# MCU.net
KiCad netlist of a schematic drawn in Altium Designer
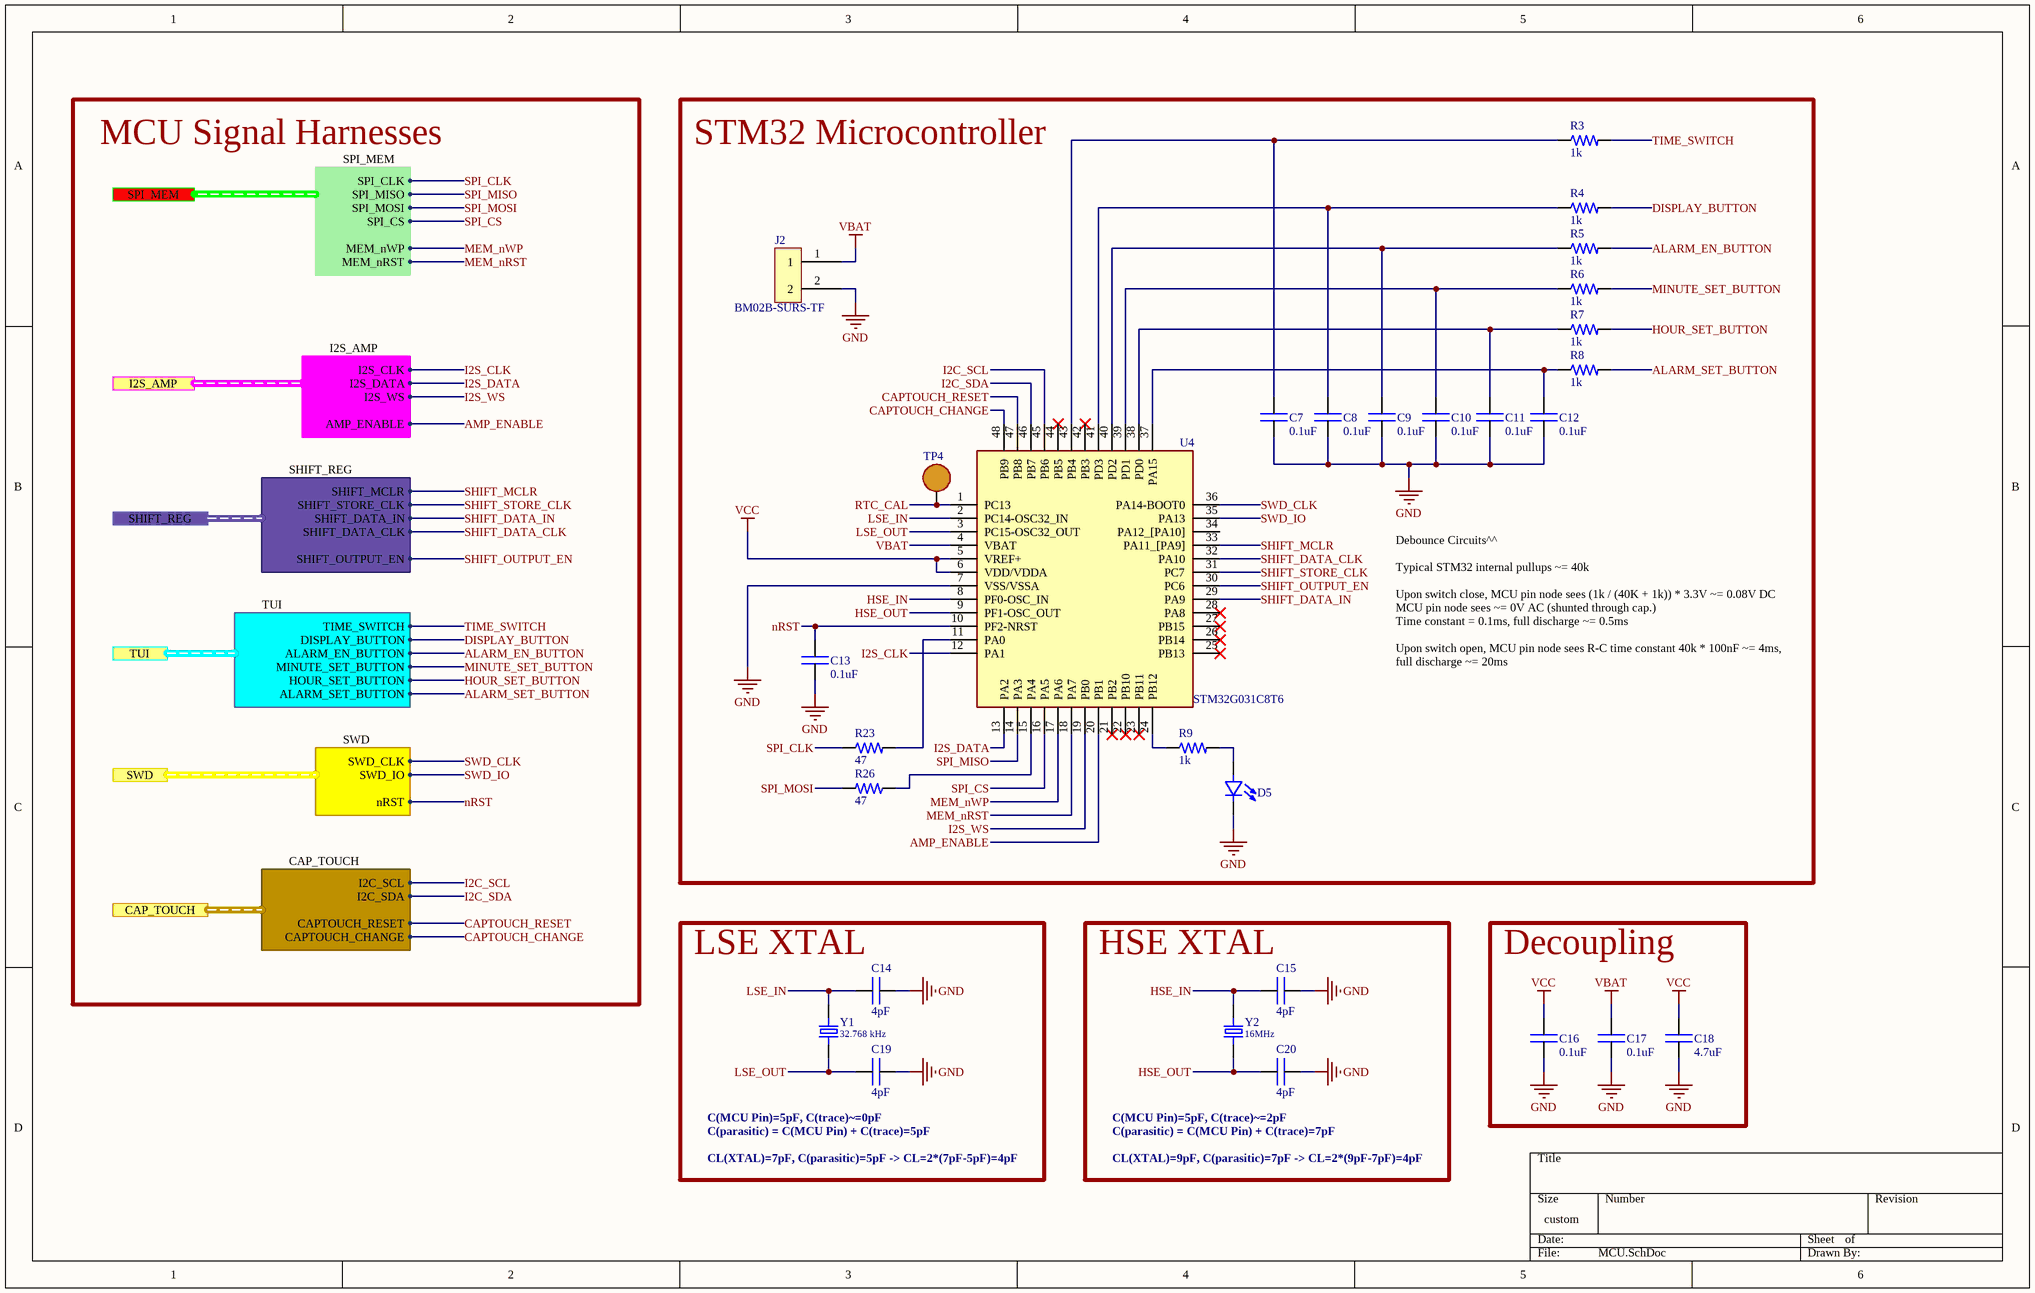
[diagram p0: MCU.SchDoc]

(export (version "E")
  (design (tool "Eeschema 10.0.6"))
  (components
    (comp (ref "C7")
      (value "0.1uF")
      (footprint "Beethoven-clock:0402C")
      (description "Capacitor")
      (fields (field (name "MFR") "Murata Electronics") (field (name "Comment") "CAP"))
      (libsource (lib "Beethoven-clock") (part "CAP"))
    )
    (comp (ref "C8")
      (value "0.1uF")
      (footprint "Beethoven-clock:0402C")
      (description "Capacitor")
      (fields (field (name "MFR") "Murata Electronics") (field (name "Comment") "CAP"))
      (libsource (lib "Beethoven-clock") (part "CAP"))
    )
    (comp (ref "C9")
      (value "0.1uF")
      (footprint "Beethoven-clock:0402C")
      (description "Capacitor")
      (fields (field (name "MFR") "Murata Electronics") (field (name "Comment") "CAP"))
      (libsource (lib "Beethoven-clock") (part "CAP"))
    )
    (comp (ref "C10")
      (value "0.1uF")
      (footprint "Beethoven-clock:0402C")
      (description "Capacitor")
      (fields (field (name "MFR") "Murata Electronics") (field (name "Comment") "CAP"))
      (libsource (lib "Beethoven-clock") (part "CAP"))
    )
    (comp (ref "C11")
      (value "0.1uF")
      (footprint "Beethoven-clock:0402C")
      (description "Capacitor")
      (fields (field (name "MFR") "Murata Electronics") (field (name "Comment") "CAP"))
      (libsource (lib "Beethoven-clock") (part "CAP"))
    )
    (comp (ref "C12")
      (value "0.1uF")
      (footprint "Beethoven-clock:0402C")
      (description "Capacitor")
      (fields (field (name "MFR") "Murata Electronics") (field (name "Comment") "CAP"))
      (libsource (lib "Beethoven-clock") (part "CAP"))
    )
    (comp (ref "C13")
      (value "0.1uF")
      (footprint "Beethoven-clock:0402C")
      (description "Capacitor")
      (fields (field (name "MFR") "Murata Electronics") (field (name "Comment") "CAP"))
      (libsource (lib "Beethoven-clock") (part "CAP"))
    )
    (comp (ref "C14")
      (value "4pF")
      (footprint "Beethoven-clock:0402C")
      (description "Capacitor")
      (fields (field (name "MFR") "YAGEO") (field (name "Comment") "CAP"))
      (libsource (lib "Beethoven-clock") (part "CAP"))
    )
    (comp (ref "C15")
      (value "4pF")
      (footprint "Beethoven-clock:0402C")
      (description "Capacitor")
      (fields (field (name "MFR") "YAGEO") (field (name "Comment") "CAP"))
      (libsource (lib "Beethoven-clock") (part "CAP"))
    )
    (comp (ref "C16")
      (value "0.1uF")
      (footprint "Beethoven-clock:0402C")
      (description "Capacitor")
      (fields (field (name "MFR") "Murata Electronics") (field (name "Comment") "CAP"))
      (libsource (lib "Beethoven-clock") (part "CAP"))
    )
    (comp (ref "C17")
      (value "0.1uF")
      (footprint "Beethoven-clock:0402C")
      (description "Capacitor")
      (fields (field (name "MFR") "Murata Electronics") (field (name "Comment") "CAP"))
      (libsource (lib "Beethoven-clock") (part "CAP"))
    )
    (comp (ref "C18")
      (value "4.7uF")
      (footprint "Beethoven-clock:0402C")
      (description "Capacitor")
      (fields (field (name "MFR") "Murata Electronics") (field (name "Comment") "CAP"))
      (libsource (lib "Beethoven-clock") (part "CAP"))
    )
    (comp (ref "C19")
      (value "4pF")
      (footprint "Beethoven-clock:0402C")
      (description "Capacitor")
      (fields (field (name "MFR") "YAGEO") (field (name "Comment") "CAP"))
      (libsource (lib "Beethoven-clock") (part "CAP"))
    )
    (comp (ref "C20")
      (value "4pF")
      (footprint "Beethoven-clock:0402C")
      (description "Capacitor")
      (fields (field (name "MFR") "YAGEO") (field (name "Comment") "CAP"))
      (libsource (lib "Beethoven-clock") (part "CAP"))
    )
    (comp (ref "D5")
      (value "LED - single")
      (footprint "Beethoven-clock:LED - 0603")
      (description "LED")
      (fields (field (name "MFR") "Dialight"))
      (libsource (lib "Beethoven-clock") (part "LED - single"))
    )
    (comp (ref "J2")
      (value "BM02B-SURS-TF")
      (footprint "Beethoven-clock:BM02B-SURS-TF")
      (description "CONN HEADER SMD 2POS 0.8MM")
      (fields (field (name "MFR") "JST"))
      (libsource (lib "Beethoven-clock") (part "CONN 2POS 0.8MM PITCH"))
    )
    (comp (ref "R3")
      (value "1k")
      (footprint "Beethoven-clock:0402R")
      (description "Resistor")
      (fields (field (name "MFR") "YAGEO") (field (name "Comment") "RES"))
      (libsource (lib "Beethoven-clock") (part "RES"))
    )
    (comp (ref "R4")
      (value "1k")
      (footprint "Beethoven-clock:0402R")
      (description "Resistor")
      (fields (field (name "MFR") "YAGEO") (field (name "Comment") "RES"))
      (libsource (lib "Beethoven-clock") (part "RES"))
    )
    (comp (ref "R5")
      (value "1k")
      (footprint "Beethoven-clock:0402R")
      (description "Resistor")
      (fields (field (name "MFR") "YAGEO") (field (name "Comment") "RES"))
      (libsource (lib "Beethoven-clock") (part "RES"))
    )
    (comp (ref "R6")
      (value "1k")
      (footprint "Beethoven-clock:0402R")
      (description "Resistor")
      (fields (field (name "MFR") "YAGEO") (field (name "Comment") "RES"))
      (libsource (lib "Beethoven-clock") (part "RES"))
    )
    (comp (ref "R7")
      (value "1k")
      (footprint "Beethoven-clock:0402R")
      (description "Resistor")
      (fields (field (name "MFR") "YAGEO") (field (name "Comment") "RES"))
      (libsource (lib "Beethoven-clock") (part "RES"))
    )
    (comp (ref "R8")
      (value "1k")
      (footprint "Beethoven-clock:0402R")
      (description "Resistor")
      (fields (field (name "MFR") "YAGEO") (field (name "Comment") "RES"))
      (libsource (lib "Beethoven-clock") (part "RES"))
    )
    (comp (ref "R9")
      (value "1k")
      (footprint "Beethoven-clock:0402R")
      (description "Resistor")
      (fields (field (name "MFR") "YAGEO") (field (name "Comment") "RES"))
      (libsource (lib "Beethoven-clock") (part "RES"))
    )
    (comp (ref "R23")
      (value "47")
      (footprint "Beethoven-clock:0402R")
      (description "Resistor")
      (fields (field (name "MFR") "YAGEO") (field (name "Comment") "RES"))
      (libsource (lib "Beethoven-clock") (part "RES"))
    )
    (comp (ref "R26")
      (value "47")
      (footprint "Beethoven-clock:0402R")
      (description "Resistor")
      (fields (field (name "MFR") "YAGEO") (field (name "Comment") "RES"))
      (libsource (lib "Beethoven-clock") (part "RES"))
    )
    (comp (ref "TP4")
      (value "RCWCTE")
      (footprint "Beethoven-clock:RCWCTE")
      (description "Test Point, Surface Mount")
      (fields (field (name "MFR") "KOA Speer Electronics, Inc."))
      (libsource (lib "Beethoven-clock") (part "TEST POINT"))
    )
    (comp (ref "U4")
      (value "STM32G031C8T6")
      (footprint "Beethoven-clock:48-LQFP")
      (fields (field (name "MFR") "STMicroelectronics"))
      (libsource (lib "Beethoven-clock") (part "STM32G031C8T6"))
    )
    (comp (ref "Y1")
      (value "32.768 kHz")
      (footprint "Beethoven-clock:ECS-.327-7-12R-TR")
      (description "SMD Tuning Fork Crystal")
      (fields (field (name "MFR") "ECS Inc."))
      (libsource (lib "Beethoven-clock") (part "32.768 kHz XTAL"))
    )
    (comp (ref "Y2")
      (value "16MHz")
      (footprint "Beethoven-clock:4-SMD_NL")
      (description "CRYSTAL 16.0000MHZ 9PF SMD")
      (fields (field (name "MFR") "EPSON"))
      (libsource (lib "Beethoven-clock") (part "16 MHz XTAL"))
    )
  )
  (nets
    (net (code "7") (name "/ALARM_EN_BUTTON") (class "Default")
      (node (ref "R5") (pin "2") (pinfunction "2_2") (pintype "passive"))
    )
    (net (code "8") (name "/ALARM_SET_BUTTON") (class "Default")
      (node (ref "R8") (pin "2") (pinfunction "2_2") (pintype "passive"))
    )
    (net (code "9") (name "/AMP_ENABLE") (class "Default")
      (node (ref "U4") (pin "20") (pinfunction "PB1_20") (pintype "passive"))
    )
    (net (code "10") (name "/CAPTOUCH_CHANGE") (class "Default")
      (node (ref "U4") (pin "48") (pinfunction "PB9_48") (pintype "passive"))
    )
    (net (code "11") (name "/CAPTOUCH_RESET") (class "Default")
      (node (ref "U4") (pin "47") (pinfunction "PB8_47") (pintype "passive"))
    )
    (net (code "12") (name "/DISPLAY_BUTTON") (class "Default")
      (node (ref "R4") (pin "2") (pinfunction "2_2") (pintype "passive"))
    )
    (net (code "13") (name "/HOUR_SET_BUTTON") (class "Default")
      (node (ref "R7") (pin "2") (pinfunction "2_2") (pintype "passive"))
    )
    (net (code "14") (name "/HSE_IN") (class "Default")
      (node (ref "C15") (pin "2") (pinfunction "2_2") (pintype "passive"))
      (node (ref "U4") (pin "8") (pinfunction "PF0-OSC_IN_8") (pintype "passive"))
      (node (ref "Y2") (pin "2") (pinfunction "2_2") (pintype "passive"))
    )
    (net (code "15") (name "/HSE_OUT") (class "Default")
      (node (ref "C20") (pin "2") (pinfunction "2_2") (pintype "passive"))
      (node (ref "U4") (pin "9") (pinfunction "PF1-OSC_OUT_9") (pintype "passive"))
      (node (ref "Y2") (pin "1") (pinfunction "1_1") (pintype "passive"))
    )
    (net (code "16") (name "/I2C_SCL") (class "Default")
      (node (ref "U4") (pin "45") (pinfunction "PB6_45") (pintype "passive"))
    )
    (net (code "17") (name "/I2C_SDA") (class "Default")
      (node (ref "U4") (pin "46") (pinfunction "PB7_46") (pintype "passive"))
    )
    (net (code "18") (name "/I2S_CLK") (class "Default")
      (node (ref "U4") (pin "12") (pinfunction "PA1_12") (pintype "passive"))
    )
    (net (code "19") (name "/I2S_DATA") (class "Default")
      (node (ref "U4") (pin "13") (pinfunction "PA2_13") (pintype "passive"))
    )
    (net (code "20") (name "/I2S_WS") (class "Default")
      (node (ref "U4") (pin "19") (pinfunction "PB0_19") (pintype "passive"))
    )
    (net (code "21") (name "/LSE_IN") (class "Default")
      (node (ref "C14") (pin "2") (pinfunction "2_2") (pintype "passive"))
      (node (ref "U4") (pin "2") (pinfunction "PC14-OSC32_IN_2") (pintype "passive"))
      (node (ref "Y1") (pin "2") (pinfunction "2_2") (pintype "passive"))
    )
    (net (code "22") (name "/LSE_OUT") (class "Default")
      (node (ref "C19") (pin "2") (pinfunction "2_2") (pintype "passive"))
      (node (ref "U4") (pin "3") (pinfunction "PC15-OSC32_OUT_3") (pintype "passive"))
      (node (ref "Y1") (pin "1") (pinfunction "1_1") (pintype "passive"))
    )
    (net (code "23") (name "/MEM_nRST") (class "Default")
      (node (ref "U4") (pin "18") (pinfunction "PA7_18") (pintype "passive"))
    )
    (net (code "24") (name "/MEM_nWP") (class "Default")
      (node (ref "U4") (pin "17") (pinfunction "PA6_17") (pintype "passive"))
    )
    (net (code "25") (name "/MINUTE_SET_BUTTON") (class "Default")
      (node (ref "R6") (pin "2") (pinfunction "2_2") (pintype "passive"))
    )
    (net (code "26") (name "/RTC_CAL") (class "Default")
      (node (ref "TP4") (pin "1") (pinfunction "0_1") (pintype "passive"))
      (node (ref "U4") (pin "1") (pinfunction "PC13_1") (pintype "passive"))
    )
    (net (code "27") (name "/SHIFT_DATA_CLK") (class "Default")
      (node (ref "U4") (pin "32") (pinfunction "PA10_32") (pintype "passive"))
    )
    (net (code "28") (name "/SHIFT_DATA_IN") (class "Default")
      (node (ref "U4") (pin "29") (pinfunction "PA9_29") (pintype "passive"))
    )
    (net (code "29") (name "/SHIFT_MCLR") (class "Default")
      (node (ref "U4") (pin "33") (pinfunction "PA11_[PA9]_33") (pintype "passive"))
    )
    (net (code "30") (name "/SHIFT_OUTPUT_EN") (class "Default")
      (node (ref "U4") (pin "30") (pinfunction "PC6_30") (pintype "passive"))
    )
    (net (code "31") (name "/SHIFT_STORE_CLK") (class "Default")
      (node (ref "U4") (pin "31") (pinfunction "PC7_31") (pintype "passive"))
    )
    (net (code "32") (name "/SPI_CLK") (class "Default")
      (node (ref "R23") (pin "1") (pinfunction "1_1") (pintype "passive"))
    )
    (net (code "33") (name "/SPI_CS") (class "Default")
      (node (ref "U4") (pin "16") (pinfunction "PA5_16") (pintype "passive"))
    )
    (net (code "34") (name "/SPI_MISO") (class "Default")
      (node (ref "U4") (pin "14") (pinfunction "PA3_14") (pintype "passive"))
    )
    (net (code "35") (name "/SPI_MOSI") (class "Default")
      (node (ref "R26") (pin "2") (pinfunction "2_2") (pintype "passive"))
    )
    (net (code "36") (name "/SWD_CLK") (class "Default")
      (node (ref "U4") (pin "36") (pinfunction "PA14-BOOT0_36") (pintype "passive"))
    )
    (net (code "37") (name "/SWD_IO") (class "Default")
      (node (ref "U4") (pin "35") (pinfunction "PA13_35") (pintype "passive"))
    )
    (net (code "38") (name "/TIME_SWITCH") (class "Default")
      (node (ref "R3") (pin "2") (pinfunction "2_2") (pintype "passive"))
    )
    (net (code "39") (name "/nRST") (class "Default")
      (node (ref "C13") (pin "2") (pinfunction "2_2") (pintype "passive"))
      (node (ref "U4") (pin "10") (pinfunction "PF2-NRST_10") (pintype "passive"))
    )
    (net (code "46") (name "GND") (class "Default")
      (node (ref "C10") (pin "1") (pinfunction "1_1") (pintype "passive"))
      (node (ref "C11") (pin "1") (pinfunction "1_1") (pintype "passive"))
      (node (ref "C12") (pin "1") (pinfunction "1_1") (pintype "passive"))
      (node (ref "C13") (pin "1") (pinfunction "1_1") (pintype "passive"))
      (node (ref "C14") (pin "1") (pinfunction "1_1") (pintype "passive"))
      (node (ref "C15") (pin "1") (pinfunction "1_1") (pintype "passive"))
      (node (ref "C16") (pin "1") (pinfunction "1_1") (pintype "passive"))
      (node (ref "C17") (pin "1") (pinfunction "1_1") (pintype "passive"))
      (node (ref "C18") (pin "1") (pinfunction "1_1") (pintype "passive"))
      (node (ref "C19") (pin "1") (pinfunction "1_1") (pintype "passive"))
      (node (ref "C20") (pin "1") (pinfunction "1_1") (pintype "passive"))
      (node (ref "C7") (pin "1") (pinfunction "1_1") (pintype "passive"))
      (node (ref "C8") (pin "1") (pinfunction "1_1") (pintype "passive"))
      (node (ref "C9") (pin "1") (pinfunction "1_1") (pintype "passive"))
      (node (ref "D5") (pin "2") (pinfunction "C_2") (pintype "passive"))
      (node (ref "J2") (pin "2") (pinfunction "2_2") (pintype "passive"))
      (node (ref "U4") (pin "7") (pinfunction "VSS/VSSA_7") (pintype "passive"))
    )
    (net (code "47") (name "Net-(D5-A)") (class "Default")
      (node (ref "D5") (pin "1") (pinfunction "A_1") (pintype "passive"))
      (node (ref "R9") (pin "2") (pinfunction "2_2") (pintype "passive"))
    )
    (net (code "48") (name "Net-(U4-PA0)") (class "Default")
      (node (ref "R23") (pin "2") (pinfunction "2_2") (pintype "passive"))
      (node (ref "U4") (pin "11") (pinfunction "PA0_11") (pintype "passive"))
    )
    (net (code "49") (name "Net-(U4-PA4)") (class "Default")
      (node (ref "R26") (pin "1") (pinfunction "1_1") (pintype "passive"))
      (node (ref "U4") (pin "15") (pinfunction "PA4_15") (pintype "passive"))
    )
    (net (code "50") (name "Net-(U4-PA15)") (class "Default")
      (node (ref "C12") (pin "2") (pinfunction "2_2") (pintype "passive"))
      (node (ref "R8") (pin "1") (pinfunction "1_1") (pintype "passive"))
      (node (ref "U4") (pin "37") (pinfunction "PA15_37") (pintype "passive"))
    )
    (net (code "51") (name "Net-(U4-PB4)") (class "Default")
      (node (ref "C7") (pin "2") (pinfunction "2_2") (pintype "passive"))
      (node (ref "R3") (pin "1") (pinfunction "1_1") (pintype "passive"))
      (node (ref "U4") (pin "43") (pinfunction "PB4_43") (pintype "passive"))
    )
    (net (code "52") (name "Net-(U4-PB12)") (class "Default")
      (node (ref "R9") (pin "1") (pinfunction "1_1") (pintype "passive"))
      (node (ref "U4") (pin "24") (pinfunction "PB12_24") (pintype "passive"))
    )
    (net (code "53") (name "Net-(U4-PD0)") (class "Default")
      (node (ref "C11") (pin "2") (pinfunction "2_2") (pintype "passive"))
      (node (ref "R7") (pin "1") (pinfunction "1_1") (pintype "passive"))
      (node (ref "U4") (pin "38") (pinfunction "PD0_38") (pintype "passive"))
    )
    (net (code "54") (name "Net-(U4-PD1)") (class "Default")
      (node (ref "C10") (pin "2") (pinfunction "2_2") (pintype "passive"))
      (node (ref "R6") (pin "1") (pinfunction "1_1") (pintype "passive"))
      (node (ref "U4") (pin "39") (pinfunction "PD1_39") (pintype "passive"))
    )
    (net (code "55") (name "Net-(U4-PD2)") (class "Default")
      (node (ref "C9") (pin "2") (pinfunction "2_2") (pintype "passive"))
      (node (ref "R5") (pin "1") (pinfunction "1_1") (pintype "passive"))
      (node (ref "U4") (pin "40") (pinfunction "PD2_40") (pintype "passive"))
    )
    (net (code "56") (name "Net-(U4-PD3)") (class "Default")
      (node (ref "C8") (pin "2") (pinfunction "2_2") (pintype "passive"))
      (node (ref "R4") (pin "1") (pinfunction "1_1") (pintype "passive"))
      (node (ref "U4") (pin "41") (pinfunction "PD3_41") (pintype "passive"))
    )
    (net (code "57") (name "VBAT") (class "Default")
      (node (ref "C17") (pin "2") (pinfunction "2_2") (pintype "passive"))
      (node (ref "J2") (pin "1") (pinfunction "1_1") (pintype "passive"))
      (node (ref "U4") (pin "4") (pinfunction "VBAT_4") (pintype "passive"))
    )
    (net (code "58") (name "VCC") (class "Default")
      (node (ref "C16") (pin "2") (pinfunction "2_2") (pintype "passive"))
      (node (ref "C18") (pin "2") (pinfunction "2_2") (pintype "passive"))
      (node (ref "U4") (pin "5") (pinfunction "VREF+_5") (pintype "passive"))
      (node (ref "U4") (pin "6") (pinfunction "VDD/VDDA_6") (pintype "passive"))
    )
    (net (code "59") (name "unconnected-(U4-PA8-Pad28)") (class "Default")
      (node (ref "U4") (pin "28") (pinfunction "PA8_28") (pintype "passive+no_connect"))
    )
    (net (code "60") (name "unconnected-(U4-PA12_[PA10]-Pad34)") (class "Default")
      (node (ref "U4") (pin "34") (pinfunction "PA12_[PA10]_34") (pintype "passive"))
    )
    (net (code "61") (name "unconnected-(U4-PB2-Pad21)") (class "Default")
      (node (ref "U4") (pin "21") (pinfunction "PB2_21") (pintype "passive+no_connect"))
    )
    (net (code "62") (name "unconnected-(U4-PB3-Pad42)") (class "Default")
      (node (ref "U4") (pin "42") (pinfunction "PB3_42") (pintype "passive+no_connect"))
    )
    (net (code "63") (name "unconnected-(U4-PB5-Pad44)") (class "Default")
      (node (ref "U4") (pin "44") (pinfunction "PB5_44") (pintype "passive+no_connect"))
    )
    (net (code "64") (name "unconnected-(U4-PB10-Pad22)") (class "Default")
      (node (ref "U4") (pin "22") (pinfunction "PB10_22") (pintype "passive+no_connect"))
    )
    (net (code "65") (name "unconnected-(U4-PB11-Pad23)") (class "Default")
      (node (ref "U4") (pin "23") (pinfunction "PB11_23") (pintype "passive+no_connect"))
    )
    (net (code "66") (name "unconnected-(U4-PB13-Pad25)") (class "Default")
      (node (ref "U4") (pin "25") (pinfunction "PB13_25") (pintype "passive+no_connect"))
    )
    (net (code "67") (name "unconnected-(U4-PB14-Pad26)") (class "Default")
      (node (ref "U4") (pin "26") (pinfunction "PB14_26") (pintype "passive+no_connect"))
    )
    (net (code "68") (name "unconnected-(U4-PB15-Pad27)") (class "Default")
      (node (ref "U4") (pin "27") (pinfunction "PB15_27") (pintype "passive+no_connect"))
    )
  )
)
